# CDRon_brushless.net
KiCad netlist of a schematic drawn in Altium Designer
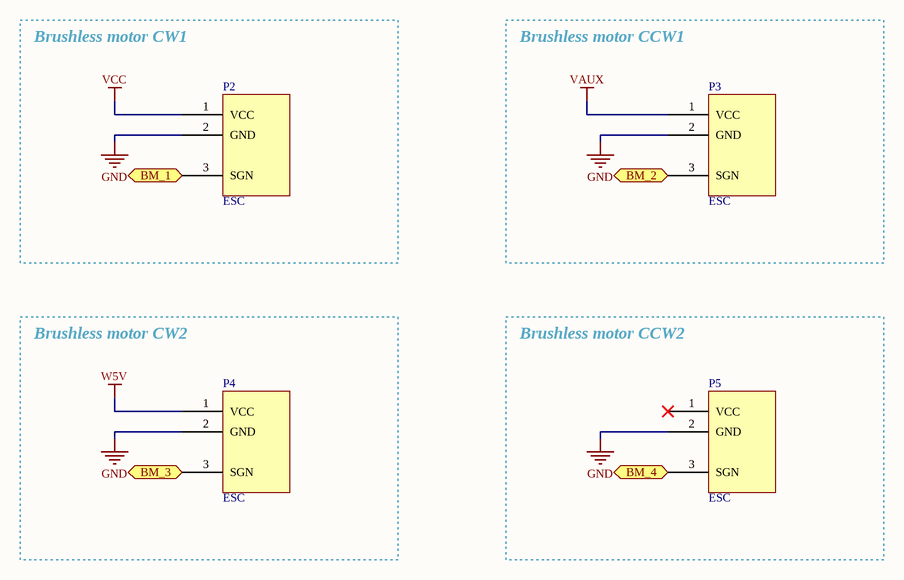
[diagram p0: CDRon_brushless.SchDoc]

(export (version "E")
  (design (tool "Eeschema 10.0.6"))
  (components
    (comp (ref "P2") (value "ESC") (footprint "ESC") (libsource (lib "CDRon_lib") (part "ESC")))
    (comp (ref "P3") (value "ESC") (footprint "ESC") (libsource (lib "CDRon_lib") (part "ESC")))
    (comp (ref "P4") (value "ESC") (footprint "ESC") (libsource (lib "CDRon_lib") (part "ESC")))
    (comp (ref "P5") (value "ESC") (footprint "ESC") (libsource (lib "CDRon_lib") (part "ESC")))
  )
  (nets
    (net (code "1") (name "/BM_1") (class "Default")
      (node (ref "P2") (pin "3") (pinfunction "SGN_3") (pintype "passive"))
    )
    (net (code "2") (name "/BM_2") (class "Default")
      (node (ref "P3") (pin "3") (pinfunction "SGN_3") (pintype "passive"))
    )
    (net (code "3") (name "/BM_3") (class "Default")
      (node (ref "P4") (pin "3") (pinfunction "SGN_3") (pintype "passive"))
    )
    (net (code "4") (name "/BM_4") (class "Default")
      (node (ref "P5") (pin "3") (pinfunction "SGN_3") (pintype "passive"))
    )
    (net (code "5") (name "GND") (class "Default")
      (node (ref "P2") (pin "2") (pinfunction "GND_2") (pintype "passive"))
      (node (ref "P3") (pin "2") (pinfunction "GND_2") (pintype "passive"))
      (node (ref "P4") (pin "2") (pinfunction "GND_2") (pintype "passive"))
      (node (ref "P5") (pin "2") (pinfunction "GND_2") (pintype "passive"))
    )
    (net (code "6") (name "VAUX") (class "Default")
      (node (ref "P3") (pin "1") (pinfunction "VCC_1") (pintype "passive"))
    )
    (net (code "7") (name "VCC") (class "Default")
      (node (ref "P2") (pin "1") (pinfunction "VCC_1") (pintype "passive"))
    )
    (net (code "8") (name "W5V") (class "Default")
      (node (ref "P4") (pin "1") (pinfunction "VCC_1") (pintype "passive"))
    )
    (net (code "9") (name "unconnected-(P5-VCC-Pad1)") (class "Default")
      (node (ref "P5") (pin "1") (pinfunction "VCC_1") (pintype "passive+no_connect"))
    )
  )
)
